# conn_harness_lv.net
KiCad netlist of a schematic drawn in Altium Designer
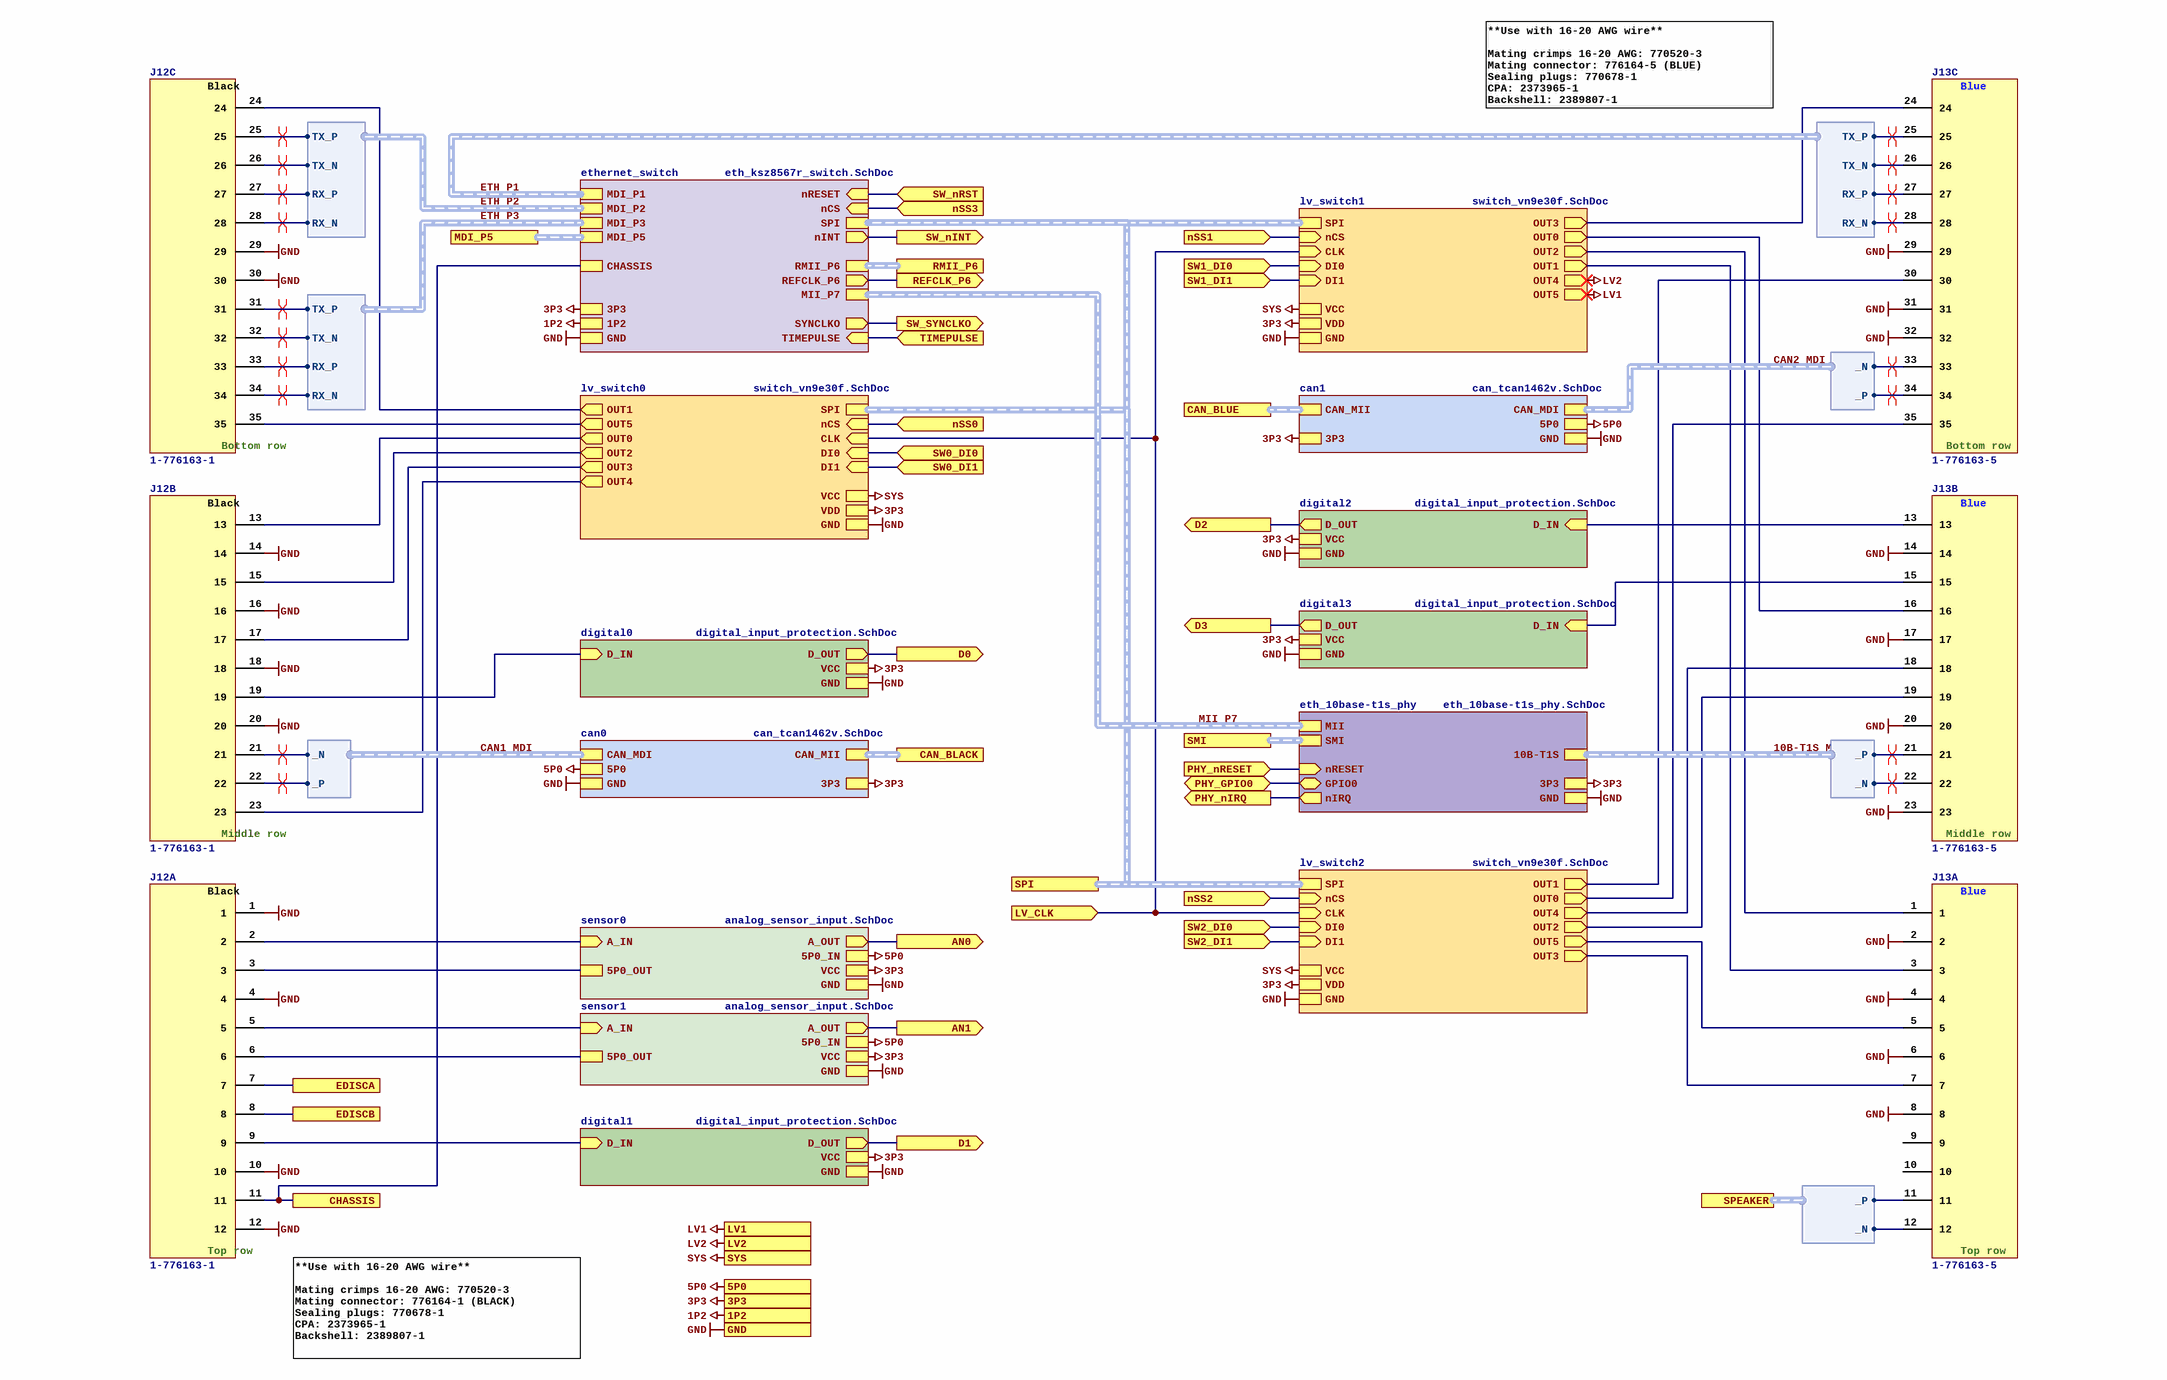
[diagram p0: conn_harness_lv.SchDoc]

(export (version "E")
  (design (tool "Eeschema 10.0.6"))
  (components
    (comp (ref "J12")
      (value "1-776163-1")
      (footprint "TE_AMPSEAL_1-776163-1")
      (description "Conn Power PL 35 POS 4mm Solder RA Thru-Hole 35 Terminal 1 Port, BLACK")
      (fields (field (name "MANUFACTURER") "TE Connectivity"))
      (libsource (lib "database") (part "1-776163-1"))
    )
    (comp (ref "J13")
      (value "1-776163-5")
      (footprint "TE_AMPSEAL_1-776163-5")
      (description "Conn Power PL 35 POS 4mm Solder RA Thru-Hole 35 Terminal 1 Port, BLUE")
      (fields (field (name "MANUFACTURER") "TE Connectivity"))
      (libsource (lib "database") (part "1-776163-5"))
    )
  )
  (nets
    (net (code "15") (name "/5P0_OUT") (class "Default")
      (node (ref "J12") (pin "6") (pinfunction "6_6") (pintype "passive"))
    )
    (net (code "16") (name "/5P0_OUT_1") (class "Default")
      (node (ref "J12") (pin "3") (pinfunction "3_3") (pintype "passive"))
    )
    (net (code "20") (name "/A_IN") (class "Default")
      (node (ref "J12") (pin "2") (pinfunction "2_2") (pintype "passive"))
    )
    (net (code "21") (name "/A_IN_1") (class "Default")
      (node (ref "J12") (pin "5") (pinfunction "5_5") (pintype "passive"))
    )
    (net (code "26") (name "/CHASSIS") (class "Default")
      (node (ref "J12") (pin "11") (pinfunction "11_11") (pintype "passive"))
    )
    (net (code "31") (name "/D_IN") (class "Default")
      (node (ref "J12") (pin "9") (pinfunction "9_9") (pintype "passive"))
    )
    (net (code "32") (name "/D_IN_1") (class "Default")
      (node (ref "J13") (pin "13") (pinfunction "13_13") (pintype "passive"))
    )
    (net (code "33") (name "/D_IN_2") (class "Default")
      (node (ref "J13") (pin "15") (pinfunction "15_15") (pintype "passive"))
    )
    (net (code "34") (name "/D_IN_3") (class "Default")
      (node (ref "J12") (pin "19") (pinfunction "19_19") (pintype "passive"))
    )
    (net (code "35") (name "/EDISCA") (class "Default")
      (node (ref "J12") (pin "7") (pinfunction "7_7") (pintype "passive"))
    )
    (net (code "36") (name "/EDISCB") (class "Default")
      (node (ref "J12") (pin "8") (pinfunction "8_8") (pintype "passive"))
    )
    (net (code "42") (name "/OUT0") (class "Default")
      (node (ref "J12") (pin "13") (pinfunction "13_13") (pintype "passive"))
    )
    (net (code "43") (name "/OUT0_1") (class "Default")
      (node (ref "J13") (pin "35") (pinfunction "35_35") (pintype "passive"))
    )
    (net (code "44") (name "/OUT0_2") (class "Default")
      (node (ref "J13") (pin "16") (pinfunction "16_16") (pintype "passive"))
    )
    (net (code "45") (name "/OUT1") (class "Default")
      (node (ref "J12") (pin "24") (pinfunction "24_24") (pintype "passive"))
    )
    (net (code "46") (name "/OUT1_1") (class "Default")
      (node (ref "J13") (pin "30") (pinfunction "30_30") (pintype "passive"))
    )
    (net (code "47") (name "/OUT1_2") (class "Default")
      (node (ref "J13") (pin "3") (pinfunction "3_3") (pintype "passive"))
    )
    (net (code "48") (name "/OUT2") (class "Default")
      (node (ref "J12") (pin "15") (pinfunction "15_15") (pintype "passive"))
    )
    (net (code "49") (name "/OUT2_1") (class "Default")
      (node (ref "J13") (pin "1") (pinfunction "1_1") (pintype "passive"))
    )
    (net (code "50") (name "/OUT2_2") (class "Default")
      (node (ref "J13") (pin "19") (pinfunction "19_19") (pintype "passive"))
    )
    (net (code "51") (name "/OUT3") (class "Default")
      (node (ref "J12") (pin "17") (pinfunction "17_17") (pintype "passive"))
    )
    (net (code "52") (name "/OUT3_1") (class "Default")
      (node (ref "J13") (pin "24") (pinfunction "24_24") (pintype "passive"))
    )
    (net (code "53") (name "/OUT3_2") (class "Default")
      (node (ref "J13") (pin "7") (pinfunction "7_7") (pintype "passive"))
    )
    (net (code "54") (name "/OUT4") (class "Default")
      (node (ref "J12") (pin "23") (pinfunction "23_23") (pintype "passive"))
    )
    (net (code "55") (name "/OUT4_1") (class "Default")
      (node (ref "J13") (pin "18") (pinfunction "18_18") (pintype "passive"))
    )
    (net (code "56") (name "/OUT5") (class "Default")
      (node (ref "J12") (pin "35") (pinfunction "35_35") (pintype "passive"))
    )
    (net (code "57") (name "/OUT5_1") (class "Default")
      (node (ref "J13") (pin "5") (pinfunction "5_5") (pintype "passive"))
    )
    (net (code "84") (name "GND") (class "Default")
      (node (ref "J12") (pin "1") (pinfunction "1_1") (pintype "passive"))
      (node (ref "J12") (pin "10") (pinfunction "10_10") (pintype "passive"))
      (node (ref "J12") (pin "12") (pinfunction "12_12") (pintype "passive"))
      (node (ref "J12") (pin "14") (pinfunction "14_14") (pintype "passive"))
      (node (ref "J12") (pin "16") (pinfunction "16_16") (pintype "passive"))
      (node (ref "J12") (pin "18") (pinfunction "18_18") (pintype "passive"))
      (node (ref "J12") (pin "20") (pinfunction "20_20") (pintype "passive"))
      (node (ref "J12") (pin "29") (pinfunction "29_29") (pintype "passive"))
      (node (ref "J12") (pin "30") (pinfunction "30_30") (pintype "passive"))
      (node (ref "J12") (pin "4") (pinfunction "4_4") (pintype "passive"))
      (node (ref "J13") (pin "14") (pinfunction "14_14") (pintype "passive"))
      (node (ref "J13") (pin "17") (pinfunction "17_17") (pintype "passive"))
      (node (ref "J13") (pin "2") (pinfunction "2_2") (pintype "passive"))
      (node (ref "J13") (pin "20") (pinfunction "20_20") (pintype "passive"))
      (node (ref "J13") (pin "23") (pinfunction "23_23") (pintype "passive"))
      (node (ref "J13") (pin "29") (pinfunction "29_29") (pintype "passive"))
      (node (ref "J13") (pin "31") (pinfunction "31_31") (pintype "passive"))
      (node (ref "J13") (pin "32") (pinfunction "32_32") (pintype "passive"))
      (node (ref "J13") (pin "4") (pinfunction "4_4") (pintype "passive"))
      (node (ref "J13") (pin "6") (pinfunction "6_6") (pintype "passive"))
      (node (ref "J13") (pin "8") (pinfunction "8_8") (pintype "passive"))
    )
    (net (code "88") (name "unconnected-(J12-Pad21)") (class "Default")
      (node (ref "J12") (pin "21") (pinfunction "21_21") (pintype "passive"))
    )
    (net (code "89") (name "unconnected-(J12-Pad22)") (class "Default")
      (node (ref "J12") (pin "22") (pinfunction "22_22") (pintype "passive"))
    )
    (net (code "90") (name "unconnected-(J12-Pad25)") (class "Default")
      (node (ref "J12") (pin "25") (pinfunction "25_25") (pintype "passive"))
    )
    (net (code "91") (name "unconnected-(J12-Pad26)") (class "Default")
      (node (ref "J12") (pin "26") (pinfunction "26_26") (pintype "passive"))
    )
    (net (code "92") (name "unconnected-(J12-Pad27)") (class "Default")
      (node (ref "J12") (pin "27") (pinfunction "27_27") (pintype "passive"))
    )
    (net (code "93") (name "unconnected-(J12-Pad28)") (class "Default")
      (node (ref "J12") (pin "28") (pinfunction "28_28") (pintype "passive"))
    )
    (net (code "94") (name "unconnected-(J12-Pad31)") (class "Default")
      (node (ref "J12") (pin "31") (pinfunction "31_31") (pintype "passive"))
    )
    (net (code "95") (name "unconnected-(J12-Pad32)") (class "Default")
      (node (ref "J12") (pin "32") (pinfunction "32_32") (pintype "passive"))
    )
    (net (code "96") (name "unconnected-(J12-Pad33)") (class "Default")
      (node (ref "J12") (pin "33") (pinfunction "33_33") (pintype "passive"))
    )
    (net (code "97") (name "unconnected-(J12-Pad34)") (class "Default")
      (node (ref "J12") (pin "34") (pinfunction "34_34") (pintype "passive"))
    )
    (net (code "98") (name "unconnected-(J13-Pad9)") (class "Default")
      (node (ref "J13") (pin "9") (pinfunction "9_9") (pintype "passive"))
    )
    (net (code "99") (name "unconnected-(J13-Pad10)") (class "Default")
      (node (ref "J13") (pin "10") (pinfunction "10_10") (pintype "passive"))
    )
    (net (code "100") (name "unconnected-(J13-Pad11)") (class "Default")
      (node (ref "J13") (pin "11") (pinfunction "11_11") (pintype "passive"))
    )
    (net (code "101") (name "unconnected-(J13-Pad12)") (class "Default")
      (node (ref "J13") (pin "12") (pinfunction "12_12") (pintype "passive"))
    )
    (net (code "102") (name "unconnected-(J13-Pad21)") (class "Default")
      (node (ref "J13") (pin "21") (pinfunction "21_21") (pintype "passive"))
    )
    (net (code "103") (name "unconnected-(J13-Pad22)") (class "Default")
      (node (ref "J13") (pin "22") (pinfunction "22_22") (pintype "passive"))
    )
    (net (code "104") (name "unconnected-(J13-Pad25)") (class "Default")
      (node (ref "J13") (pin "25") (pinfunction "25_25") (pintype "passive"))
    )
    (net (code "105") (name "unconnected-(J13-Pad26)") (class "Default")
      (node (ref "J13") (pin "26") (pinfunction "26_26") (pintype "passive"))
    )
    (net (code "106") (name "unconnected-(J13-Pad27)") (class "Default")
      (node (ref "J13") (pin "27") (pinfunction "27_27") (pintype "passive"))
    )
    (net (code "107") (name "unconnected-(J13-Pad28)") (class "Default")
      (node (ref "J13") (pin "28") (pinfunction "28_28") (pintype "passive"))
    )
    (net (code "108") (name "unconnected-(J13-Pad33)") (class "Default")
      (node (ref "J13") (pin "33") (pinfunction "33_33") (pintype "passive"))
    )
    (net (code "109") (name "unconnected-(J13-Pad34)") (class "Default")
      (node (ref "J13") (pin "34") (pinfunction "34_34") (pintype "passive"))
    )
  )
)
